# SCH8_BBB.net
KiCad netlist of a schematic drawn in Altium Designer
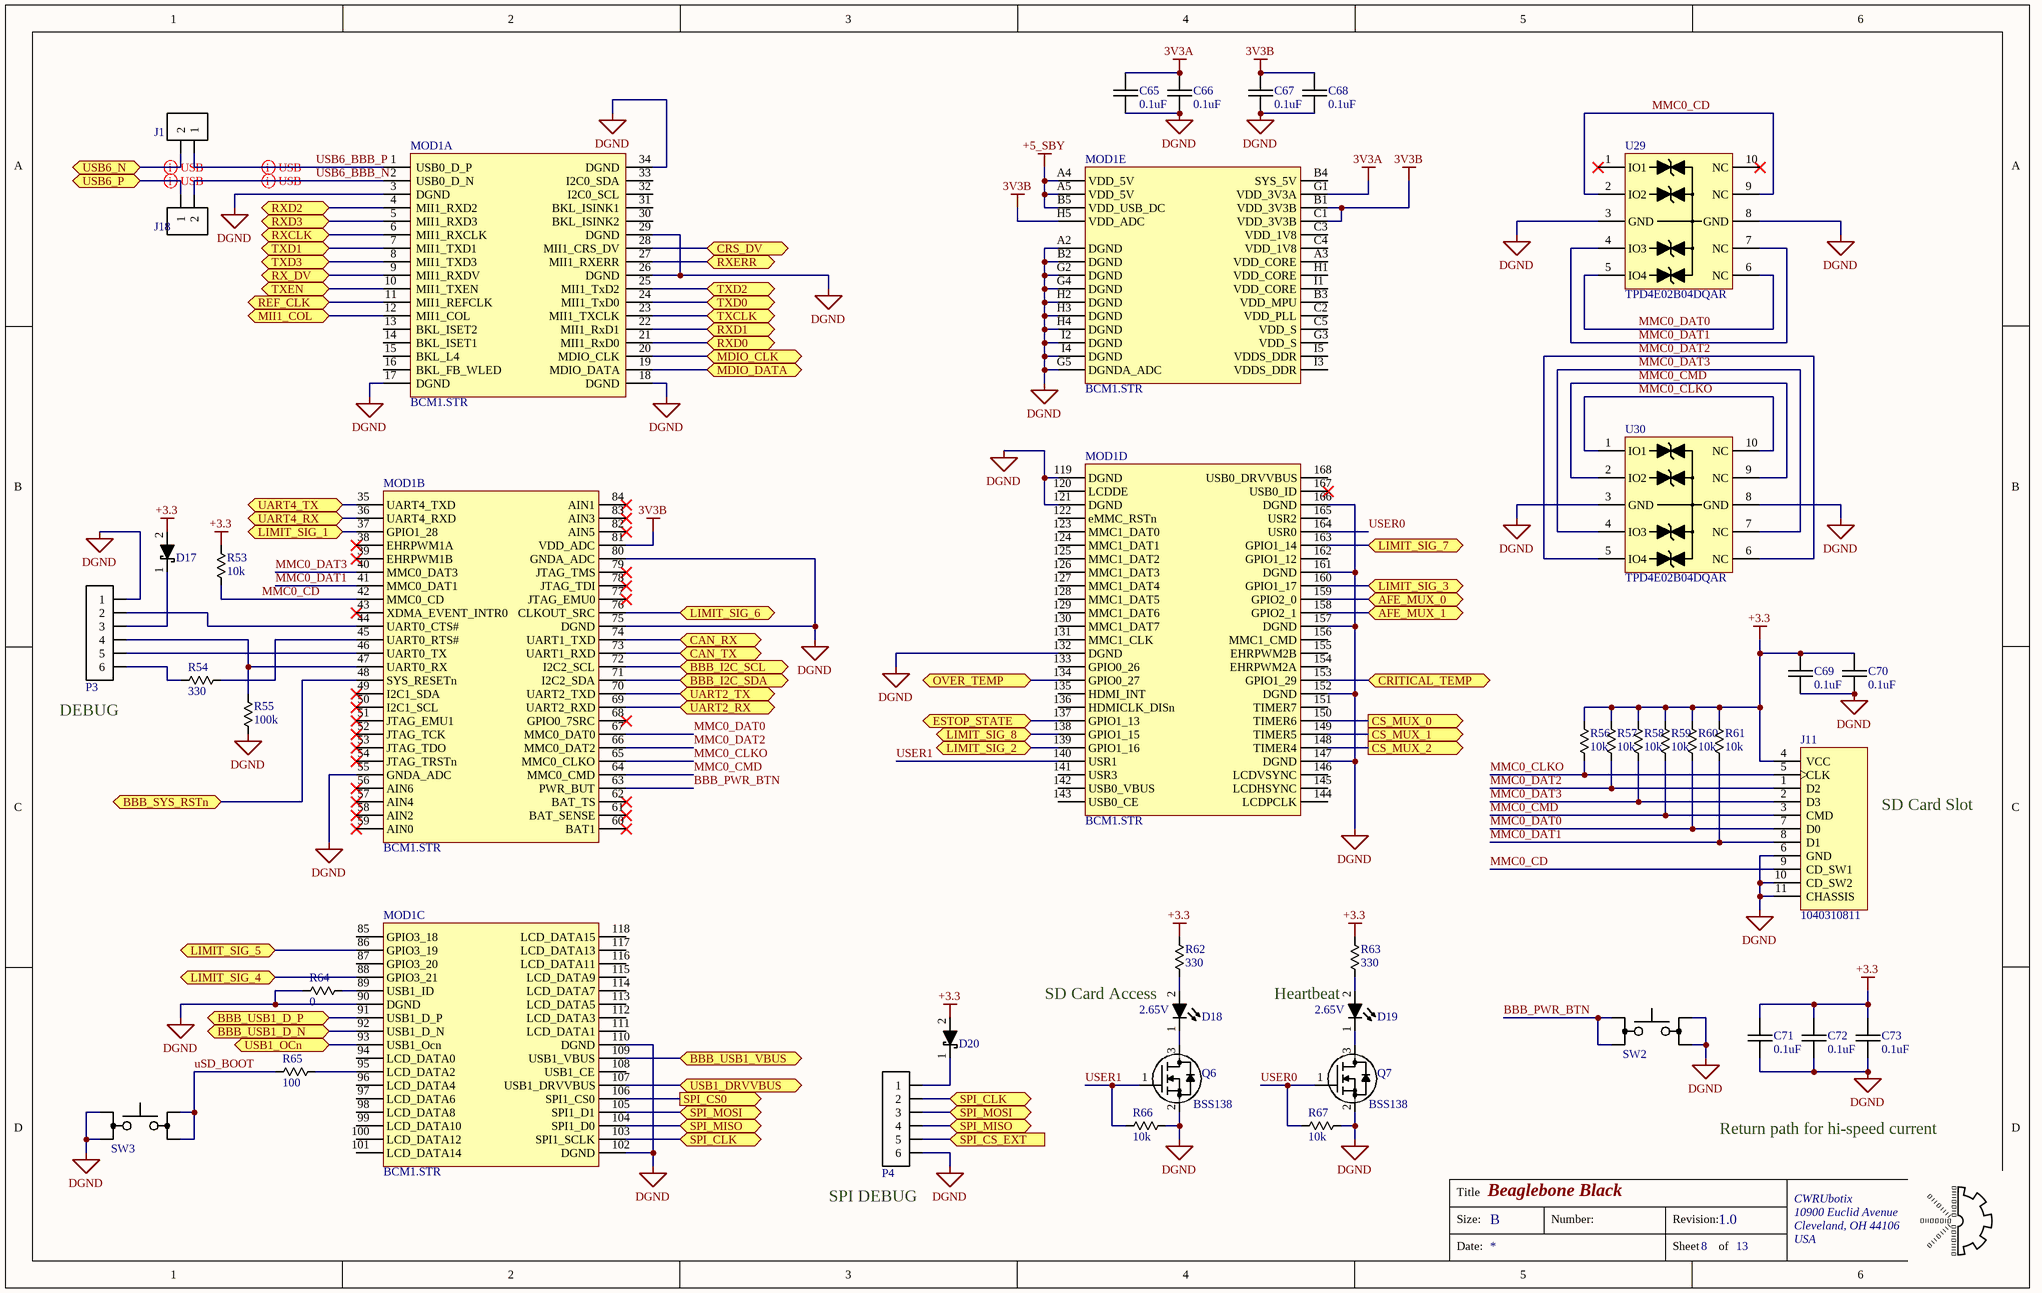
[diagram p0: SCH8_BBB.SchDoc]

(export (version "E")
  (design (tool "Eeschema 10.0.6"))
  (components
    (comp (ref "C65")
      (value "0.1uF")
      (footprint "chip_0603")
      (description "CAP, 0.1uF, ±10%, 16V, X7R, 0603")
      (fields (field (name "PART NUMBER") "CAP-00542") (field (name "TOLERANCE") "±10%"))
      (libsource (lib "Capacitors$") (part "CAP-00542"))
    )
    (comp (ref "C66")
      (value "0.1uF")
      (footprint "chip_0603")
      (description "CAP, 0.1uF, ±10%, 16V, X7R, 0603")
      (fields (field (name "PART NUMBER") "CAP-00542") (field (name "TOLERANCE") "±10%"))
      (libsource (lib "Capacitors$") (part "CAP-00542"))
    )
    (comp (ref "C67")
      (value "0.1uF")
      (footprint "chip_0603")
      (description "CAP, 0.1uF, ±10%, 16V, X7R, 0603")
      (fields (field (name "PART NUMBER") "CAP-00542") (field (name "TOLERANCE") "±10%"))
      (libsource (lib "Capacitors$") (part "CAP-00542"))
    )
    (comp (ref "C68")
      (value "0.1uF")
      (footprint "chip_0603")
      (description "CAP, 0.1uF, ±10%, 16V, X7R, 0603")
      (fields (field (name "PART NUMBER") "CAP-00542") (field (name "TOLERANCE") "±10%"))
      (libsource (lib "Capacitors$") (part "CAP-00542"))
    )
    (comp (ref "C69")
      (value "0.1uF")
      (footprint "chip_0603")
      (description "CAP, 0.1uF, ±10%, 16V, X7R, 0603")
      (fields (field (name "PART NUMBER") "CAP-00542") (field (name "TOLERANCE") "±10%"))
      (libsource (lib "Capacitors$") (part "CAP-00542"))
    )
    (comp (ref "C70")
      (value "0.1uF")
      (footprint "chip_0603")
      (description "CAP, 0.1uF, ±10%, 16V, X7R, 0603")
      (fields (field (name "PART NUMBER") "CAP-00542") (field (name "TOLERANCE") "±10%"))
      (libsource (lib "Capacitors$") (part "CAP-00542"))
    )
    (comp (ref "C71")
      (value "0.1uF")
      (footprint "chip_0603")
      (description "CAP, 0.1uF, ±10%, 16V, X7R, 0603")
      (fields (field (name "PART NUMBER") "CAP-00542") (field (name "TOLERANCE") "±10%"))
      (libsource (lib "Capacitors$") (part "CAP-00542"))
    )
    (comp (ref "C72")
      (value "0.1uF")
      (footprint "chip_0603")
      (description "CAP, 0.1uF, ±10%, 16V, X7R, 0603")
      (fields (field (name "PART NUMBER") "CAP-00542") (field (name "TOLERANCE") "±10%"))
      (libsource (lib "Capacitors$") (part "CAP-00542"))
    )
    (comp (ref "C73")
      (value "0.1uF")
      (footprint "chip_0603")
      (description "CAP, 0.1uF, ±10%, 16V, X7R, 0603")
      (fields (field (name "PART NUMBER") "CAP-00542") (field (name "TOLERANCE") "±10%"))
      (libsource (lib "Capacitors$") (part "CAP-00542"))
    )
    (comp (ref "D17")
      (value "diode_2")
      (footprint "sod123_0")
      (description "Dio Shtky, 1A, 0.55V, 40V, SOD-123")
      (fields (field (name "PART NUMBER") "DIO-00001") (field (name "MANUFACTURER") "ON Semi"))
      (libsource (lib "Diodes$") (part "DIO-00001"))
    )
    (comp (ref "D18")
      (value "diode_4")
      (footprint "chip_0603_LED")
      (description "LED, Blue, 0603, Low current, HELI2 Series")
      (fields
        (field (name "PART NUMBER") "DIO-00049")
        (field (name "FORWARD VOLTAGE") "2.65V")
        (field (name "MANUFACTURER") "Kingbright")
      )
      (libsource (lib "Diodes$") (part "DIO-00049"))
    )
    (comp (ref "D19")
      (value "diode_4")
      (footprint "chip_0603_LED")
      (description "LED, Blue, 0603, Low current, HELI2 Series")
      (fields
        (field (name "PART NUMBER") "DIO-00049")
        (field (name "FORWARD VOLTAGE") "2.65V")
        (field (name "MANUFACTURER") "Kingbright")
      )
      (libsource (lib "Diodes$") (part "DIO-00049"))
    )
    (comp (ref "D20")
      (value "diode_2")
      (footprint "sod123_0")
      (description "Dio Shtky, 1A, 0.55V, 40V, SOD-123")
      (fields (field (name "PART NUMBER") "DIO-00001") (field (name "MANUFACTURER") "ON Semi"))
      (libsource (lib "Diodes$") (part "DIO-00001"))
    )
    (comp (ref "J1")
      (value "conn-2x1_0")
      (footprint "HDDR_2x1_0")
      (description "Header, 2x1, 0.1\"")
      (fields (field (name "PART NUMBER") "CONN-00055") (field (name "MANUFACTURER") "Samtec"))
      (libsource (lib "Connectors$") (part "CONN-00055"))
    )
    (comp (ref "J11")
      (value "1040310811")
      (footprint "MOLEX_1040310811")
      (description "Micro SD Card Slot, Push-Pull w/ Card-Detect Switch, SMD, Molex")
      (fields (field (name "PART NUMBER") "CONN-00091") (field (name "MANUFACTURER") "Molex"))
      (libsource (lib "Connectors$") (part "CONN-00091"))
    )
    (comp (ref "J18")
      (value "conn-2x1_0")
      (footprint "HDDR_2x1_0")
      (description "Header, 2x1, 0.1\"")
      (fields (field (name "PART NUMBER") "CONN-00055") (field (name "MANUFACTURER") "Samtec"))
      (libsource (lib "Connectors$") (part "CONN-00055"))
    )
    (comp (ref "MOD1")
      (value "BCM1.STR")
      (footprint "BEAGLECORE_BCM1")
      (description "BeagleCore BCM1, System-On-Module (SOM)")
      (fields (field (name "PART NUMBER") "UCTRL-00011") (field (name "MANUFACTURER") "BeagleCore"))
      (libsource (lib "Microcontrollers$") (part "UCTRL-00011"))
    )
    (comp (ref "P3")
      (value "conn-6x1_0")
      (footprint "HDDR_6X1_0")
      (description "Header 6x1, 0.1\"")
      (fields (field (name "PART NUMBER") "CONN-00008"))
      (libsource (lib "Connectors$") (part "CONN-00008"))
    )
    (comp (ref "P4")
      (value "conn-6x1_0")
      (footprint "HDDR_6X1_0")
      (description "Header 6x1, 0.1\"")
      (fields (field (name "PART NUMBER") "CONN-00008"))
      (libsource (lib "Connectors$") (part "CONN-00008"))
    )
    (comp (ref "Q6")
      (value "n-mosfet_1")
      (footprint "sot-23-3")
      (description "XSTR NMOS, 220mA, 50V, Vgs 1.3V, SOT-23-3")
      (fields
        (field (name "PART NUMBER") "XSTR-00017")
        (field (name "MANUFACTURER") "ON Semi")
        (field (name "MANUFACTURER PN") "BSS138")
      )
      (libsource (lib "Transistors$") (part "XSTR-00017"))
    )
    (comp (ref "Q7")
      (value "n-mosfet_1")
      (footprint "sot-23-3")
      (description "XSTR NMOS, 220mA, 50V, Vgs 1.3V, SOT-23-3")
      (fields
        (field (name "PART NUMBER") "XSTR-00017")
        (field (name "MANUFACTURER") "ON Semi")
        (field (name "MANUFACTURER PN") "BSS138")
      )
      (libsource (lib "Transistors$") (part "XSTR-00017"))
    )
    (comp (ref "R53")
      (value "10k")
      (footprint "chip_0603")
      (description "RES SMD 10K OHM 1% 1/4W 0603")
      (fields (field (name "PART NUMBER") "RES-00306") (field (name "TOLERANCE") "1%"))
      (libsource (lib "Resistors$") (part "RES-00306"))
    )
    (comp (ref "R54")
      (value "330")
      (footprint "chip_0603")
      (description "RES SMD 330 OHM 1% 1/4W 0603")
      (fields (field (name "PART NUMBER") "RES-00221") (field (name "TOLERANCE") "1%"))
      (libsource (lib "Resistors$") (part "RES-00221"))
    )
    (comp (ref "R55")
      (value "100k")
      (footprint "chip_0603")
      (description "RES SMD 100K OHM 1% 1/4W 0603")
      (fields (field (name "PART NUMBER") "RES-00301") (field (name "TOLERANCE") "1%"))
      (libsource (lib "Resistors$") (part "RES-00301"))
    )
    (comp (ref "R56")
      (value "10k")
      (footprint "chip_0603")
      (description "RES SMD 10K OHM 1% 1/4W 0603")
      (fields (field (name "PART NUMBER") "RES-00306") (field (name "TOLERANCE") "1%"))
      (libsource (lib "Resistors$") (part "RES-00306"))
    )
    (comp (ref "R57")
      (value "10k")
      (footprint "chip_0603")
      (description "RES SMD 10K OHM 1% 1/4W 0603")
      (fields (field (name "PART NUMBER") "RES-00306") (field (name "TOLERANCE") "1%"))
      (libsource (lib "Resistors$") (part "RES-00306"))
    )
    (comp (ref "R58")
      (value "10k")
      (footprint "chip_0603")
      (description "RES SMD 10K OHM 1% 1/4W 0603")
      (fields (field (name "PART NUMBER") "RES-00306") (field (name "TOLERANCE") "1%"))
      (libsource (lib "Resistors$") (part "RES-00306"))
    )
    (comp (ref "R59")
      (value "10k")
      (footprint "chip_0603")
      (description "RES SMD 10K OHM 1% 1/4W 0603")
      (fields (field (name "PART NUMBER") "RES-00306") (field (name "TOLERANCE") "1%"))
      (libsource (lib "Resistors$") (part "RES-00306"))
    )
    (comp (ref "R60")
      (value "10k")
      (footprint "chip_0603")
      (description "RES SMD 10K OHM 1% 1/4W 0603")
      (fields (field (name "PART NUMBER") "RES-00306") (field (name "TOLERANCE") "1%"))
      (libsource (lib "Resistors$") (part "RES-00306"))
    )
    (comp (ref "R61")
      (value "10k")
      (footprint "chip_0603")
      (description "RES SMD 10K OHM 1% 1/4W 0603")
      (fields (field (name "PART NUMBER") "RES-00306") (field (name "TOLERANCE") "1%"))
      (libsource (lib "Resistors$") (part "RES-00306"))
    )
    (comp (ref "R62")
      (value "330")
      (footprint "chip_0603")
      (description "RES SMD 330 OHM 1% 1/4W 0603")
      (fields (field (name "PART NUMBER") "RES-00221") (field (name "TOLERANCE") "1%"))
      (libsource (lib "Resistors$") (part "RES-00221"))
    )
    (comp (ref "R63")
      (value "330")
      (footprint "chip_0603")
      (description "RES SMD 330 OHM 1% 1/4W 0603")
      (fields (field (name "PART NUMBER") "RES-00221") (field (name "TOLERANCE") "1%"))
      (libsource (lib "Resistors$") (part "RES-00221"))
    )
    (comp (ref "R64")
      (value "0")
      (footprint "chip_0805")
      (description "RES SMD 0 OHM 1/8W 0805 Thick Film")
      (fields (field (name "PART NUMBER") "RES-00720") (field (name "TOLERANCE") "Jumper"))
      (libsource (lib "Resistors$") (part "RES-00720"))
    )
    (comp (ref "R65")
      (value "100")
      (footprint "chip_0603")
      (description "RES SMD 100 OHM 1% 1/4W 0603")
      (fields (field (name "PART NUMBER") "RES-00178") (field (name "TOLERANCE") "1%"))
      (libsource (lib "Resistors$") (part "RES-00178"))
    )
    (comp (ref "R66")
      (value "10k")
      (footprint "chip_0603")
      (description "RES SMD 10K OHM 1% 1/4W 0603")
      (fields (field (name "PART NUMBER") "RES-00306") (field (name "TOLERANCE") "1%"))
      (libsource (lib "Resistors$") (part "RES-00306"))
    )
    (comp (ref "R67")
      (value "10k")
      (footprint "chip_0603")
      (description "RES SMD 10K OHM 1% 1/4W 0603")
      (fields (field (name "PART NUMBER") "RES-00306") (field (name "TOLERANCE") "1%"))
      (libsource (lib "Resistors$") (part "RES-00306"))
    )
    (comp (ref "SW2")
      (value "SW_1P1T_2")
      (footprint "B3FS-1000")
      (description "Switch, SPST-NO, Tactile, 6.3x6.0mm, SMD, 50mA 24VDC")
      (fields (field (name "PART NUMBER") "MISC-00042") (field (name "MANUFACTURER") "Omron"))
      (libsource (lib "Misc$") (part "MISC-00042"))
    )
    (comp (ref "SW3")
      (value "SW_1P1T_2")
      (footprint "B3FS-1000")
      (description "Switch, SPST-NO, Tactile, 6.3x6.0mm, SMD, 50mA 24VDC")
      (fields (field (name "PART NUMBER") "MISC-00042") (field (name "MANUFACTURER") "Omron"))
      (libsource (lib "Misc$") (part "MISC-00042"))
    )
    (comp (ref "U29")
      (value "TPD4E02B04DQAR")
      (footprint "USON-10")
      (description "TVS, 4-Ch, ESD Protec, 3.6V 8.8V 10-USON")
      (fields (field (name "PART NUMBER") "DIO-00068") (field (name "MANUFACTURER") "TI"))
      (libsource (lib "Diodes$") (part "DIO-00068"))
    )
    (comp (ref "U30")
      (value "TPD4E02B04DQAR")
      (footprint "USON-10")
      (description "TVS, 4-Ch, ESD Protec, 3.6V 8.8V 10-USON")
      (fields (field (name "PART NUMBER") "DIO-00068") (field (name "MANUFACTURER") "TI"))
      (libsource (lib "Diodes$") (part "DIO-00068"))
    )
  )
  (nets
    (net (code "1") (name "+3.3") (class "Default")
      (node (ref "C69") (pin "2") (pinfunction "2_2") (pintype "passive"))
      (node (ref "C70") (pin "2") (pinfunction "2_2") (pintype "passive"))
      (node (ref "C71") (pin "2") (pinfunction "2_2") (pintype "passive"))
      (node (ref "C72") (pin "2") (pinfunction "2_2") (pintype "passive"))
      (node (ref "C73") (pin "2") (pinfunction "2_2") (pintype "passive"))
      (node (ref "D17") (pin "2") (pinfunction "2_2") (pintype "passive"))
      (node (ref "D20") (pin "2") (pinfunction "2_2") (pintype "passive"))
      (node (ref "J11") (pin "4") (pinfunction "VCC_4") (pintype "passive"))
      (node (ref "R53") (pin "1") (pinfunction "1_1") (pintype "passive"))
      (node (ref "R56") (pin "1") (pinfunction "1_1") (pintype "passive"))
      (node (ref "R57") (pin "1") (pinfunction "1_1") (pintype "passive"))
      (node (ref "R58") (pin "1") (pinfunction "1_1") (pintype "passive"))
      (node (ref "R59") (pin "1") (pinfunction "1_1") (pintype "passive"))
      (node (ref "R60") (pin "1") (pinfunction "1_1") (pintype "passive"))
      (node (ref "R61") (pin "1") (pinfunction "1_1") (pintype "passive"))
      (node (ref "R62") (pin "2") (pinfunction "2_2") (pintype "passive"))
      (node (ref "R63") (pin "2") (pinfunction "2_2") (pintype "passive"))
    )
    (net (code "2") (name "+5_SBY") (class "Default")
      (node (ref "MOD1") (pin "A4") (pinfunction "VDD_5V_A4") (pintype "passive"))
      (node (ref "MOD1") (pin "A5") (pinfunction "VDD_5V_A5") (pintype "passive"))
      (node (ref "MOD1") (pin "B5") (pinfunction "VDD_USB_DC_B5") (pintype "passive"))
    )
    (net (code "3") (name "/AFE_MUX_0") (class "Default")
      (node (ref "MOD1") (pin "159") (pinfunction "GPIO2_0_159") (pintype "passive"))
    )
    (net (code "4") (name "/AFE_MUX_1") (class "Default")
      (node (ref "MOD1") (pin "158") (pinfunction "GPIO2_1_158") (pintype "passive"))
    )
    (net (code "5") (name "/BBB_I2C_SCL") (class "Default")
      (node (ref "MOD1") (pin "72") (pinfunction "I2C2_SCL_72") (pintype "passive"))
    )
    (net (code "6") (name "/BBB_I2C_SDA") (class "Default")
      (node (ref "MOD1") (pin "71") (pinfunction "I2C2_SDA_71") (pintype "passive"))
    )
    (net (code "7") (name "/BBB_PWR_BTN") (class "Default")
      (node (ref "MOD1") (pin "63") (pinfunction "PWR_BUT_63") (pintype "passive"))
      (node (ref "SW2") (pin "1") (pinfunction "1_1") (pintype "passive"))
      (node (ref "SW2") (pin "2") (pinfunction "2_2") (pintype "passive"))
    )
    (net (code "8") (name "/BBB_SYS_RSTn") (class "Default")
      (node (ref "MOD1") (pin "48") (pinfunction "SYS_RESETn_48") (pintype "passive"))
    )
    (net (code "9") (name "/BBB_USB1_D_N") (class "Default")
      (node (ref "MOD1") (pin "92") (pinfunction "USB1_D_N_92") (pintype "passive"))
    )
    (net (code "10") (name "/BBB_USB1_D_P") (class "Default")
      (node (ref "MOD1") (pin "91") (pinfunction "USB1_D_P_91") (pintype "passive"))
    )
    (net (code "11") (name "/BBB_USB1_VBUS") (class "Default")
      (node (ref "MOD1") (pin "109") (pinfunction "USB1_VBUS_109") (pintype "passive"))
    )
    (net (code "12") (name "/CAN_RX") (class "Default")
      (node (ref "MOD1") (pin "74") (pinfunction "UART1_TXD_74") (pintype "passive"))
    )
    (net (code "13") (name "/CAN_TX") (class "Default")
      (node (ref "MOD1") (pin "73") (pinfunction "UART1_RXD_73") (pintype "passive"))
    )
    (net (code "14") (name "/CRITICAL_TEMP") (class "Default")
      (node (ref "MOD1") (pin "153") (pinfunction "GPIO1_29_153") (pintype "passive"))
    )
    (net (code "15") (name "/CRS_DV") (class "Default")
      (node (ref "MOD1") (pin "28") (pinfunction "MII1_CRS_DV_28") (pintype "passive"))
    )
    (net (code "16") (name "/CS_MUX_0") (class "Default")
      (node (ref "MOD1") (pin "150") (pinfunction "TIMER6_150") (pintype "passive"))
    )
    (net (code "17") (name "/CS_MUX_1") (class "Default")
      (node (ref "MOD1") (pin "149") (pinfunction "TIMER5_149") (pintype "passive"))
    )
    (net (code "18") (name "/CS_MUX_2") (class "Default")
      (node (ref "MOD1") (pin "148") (pinfunction "TIMER4_148") (pintype "passive"))
    )
    (net (code "19") (name "/ESTOP_STATE") (class "Default")
      (node (ref "MOD1") (pin "137") (pinfunction "GPIO1_13_137") (pintype "passive"))
    )
    (net (code "20") (name "/LIMIT_SIG_1") (class "Default")
      (node (ref "MOD1") (pin "37") (pinfunction "GPIO1_28_37") (pintype "passive"))
    )
    (net (code "21") (name "/LIMIT_SIG_2") (class "Default")
      (node (ref "MOD1") (pin "139") (pinfunction "GPIO1_16_139") (pintype "passive"))
    )
    (net (code "22") (name "/LIMIT_SIG_3") (class "Default")
      (node (ref "MOD1") (pin "160") (pinfunction "GPIO1_17_160") (pintype "passive"))
    )
    (net (code "23") (name "/LIMIT_SIG_4") (class "Default")
      (node (ref "MOD1") (pin "88") (pinfunction "GPIO3_21_88") (pintype "passive"))
    )
    (net (code "24") (name "/LIMIT_SIG_5") (class "Default")
      (node (ref "MOD1") (pin "86") (pinfunction "GPIO3_19_86") (pintype "passive"))
    )
    (net (code "25") (name "/LIMIT_SIG_6") (class "Default")
      (node (ref "MOD1") (pin "76") (pinfunction "CLKOUT_SRC_76") (pintype "passive"))
    )
    (net (code "26") (name "/LIMIT_SIG_7") (class "Default")
      (node (ref "MOD1") (pin "163") (pinfunction "GPIO1_14_163") (pintype "passive"))
    )
    (net (code "27") (name "/LIMIT_SIG_8") (class "Default")
      (node (ref "MOD1") (pin "138") (pinfunction "GPIO1_15_138") (pintype "passive"))
    )
    (net (code "28") (name "/MDIO_CLK") (class "Default")
      (node (ref "MOD1") (pin "20") (pinfunction "MDIO_CLK_20") (pintype "passive"))
    )
    (net (code "29") (name "/MDIO_DATA") (class "Default")
      (node (ref "MOD1") (pin "19") (pinfunction "MDIO_DATA_19") (pintype "passive"))
    )
    (net (code "30") (name "/MII1_COL") (class "Default")
      (node (ref "MOD1") (pin "12") (pinfunction "MII1_COL_12") (pintype "passive"))
    )
    (net (code "31") (name "/MMC0_CD") (class "Default")
      (node (ref "J11") (pin "9") (pinfunction "CD_SW1_9") (pintype "passive"))
      (node (ref "MOD1") (pin "42") (pinfunction "MMC0_CD_42") (pintype "passive"))
      (node (ref "R53") (pin "2") (pinfunction "2_2") (pintype "passive"))
      (node (ref "U29") (pin "2") (pinfunction "IO2_2") (pintype "passive"))
      (node (ref "U29") (pin "9") (pinfunction "NC_9") (pintype "passive"))
    )
    (net (code "32") (name "/MMC0_CLKO") (class "Default")
      (node (ref "J11") (pin "5") (pinfunction "CLK_5") (pintype "passive"))
      (node (ref "MOD1") (pin "65") (pinfunction "MMC0_CLKO_65") (pintype "passive"))
      (node (ref "R56") (pin "2") (pinfunction "2_2") (pintype "passive"))
      (node (ref "U30") (pin "1") (pinfunction "IO1_1") (pintype "passive"))
      (node (ref "U30") (pin "10") (pinfunction "NC_10") (pintype "passive"))
    )
    (net (code "33") (name "/MMC0_CMD") (class "Default")
      (node (ref "J11") (pin "3") (pinfunction "CMD_3") (pintype "passive"))
      (node (ref "MOD1") (pin "64") (pinfunction "MMC0_CMD_64") (pintype "passive"))
      (node (ref "R59") (pin "2") (pinfunction "2_2") (pintype "passive"))
      (node (ref "U30") (pin "2") (pinfunction "IO2_2") (pintype "passive"))
      (node (ref "U30") (pin "9") (pinfunction "NC_9") (pintype "passive"))
    )
    (net (code "34") (name "/MMC0_DAT0") (class "Default")
      (node (ref "J11") (pin "7") (pinfunction "D0_7") (pintype "passive"))
      (node (ref "MOD1") (pin "67") (pinfunction "MMC0_DAT0_67") (pintype "passive"))
      (node (ref "R60") (pin "2") (pinfunction "2_2") (pintype "passive"))
      (node (ref "U29") (pin "5") (pinfunction "IO4_5") (pintype "passive"))
      (node (ref "U29") (pin "6") (pinfunction "NC_6") (pintype "passive"))
    )
    (net (code "35") (name "/MMC0_DAT1") (class "Default")
      (node (ref "J11") (pin "8") (pinfunction "D1_8") (pintype "passive"))
      (node (ref "MOD1") (pin "41") (pinfunction "MMC0_DAT1_41") (pintype "passive"))
      (node (ref "R61") (pin "2") (pinfunction "2_2") (pintype "passive"))
      (node (ref "U29") (pin "4") (pinfunction "IO3_4") (pintype "passive"))
      (node (ref "U29") (pin "7") (pinfunction "NC_7") (pintype "passive"))
    )
    (net (code "36") (name "/MMC0_DAT2") (class "Default")
      (node (ref "J11") (pin "1") (pinfunction "D2_1") (pintype "passive"))
      (node (ref "MOD1") (pin "66") (pinfunction "MMC0_DAT2_66") (pintype "passive"))
      (node (ref "R57") (pin "2") (pinfunction "2_2") (pintype "passive"))
      (node (ref "U30") (pin "5") (pinfunction "IO4_5") (pintype "passive"))
      (node (ref "U30") (pin "6") (pinfunction "NC_6") (pintype "passive"))
    )
    (net (code "37") (name "/MMC0_DAT3") (class "Default")
      (node (ref "J11") (pin "2") (pinfunction "D3_2") (pintype "passive"))
      (node (ref "MOD1") (pin "40") (pinfunction "MMC0_DAT3_40") (pintype "passive"))
      (node (ref "R58") (pin "2") (pinfunction "2_2") (pintype "passive"))
      (node (ref "U30") (pin "4") (pinfunction "IO3_4") (pintype "passive"))
      (node (ref "U30") (pin "7") (pinfunction "NC_7") (pintype "passive"))
    )
    (net (code "38") (name "/OVER_TEMP") (class "Default")
      (node (ref "MOD1") (pin "134") (pinfunction "GPIO0_27_134") (pintype "passive"))
    )
    (net (code "39") (name "/REF_CLK") (class "Default")
      (node (ref "MOD1") (pin "11") (pinfunction "MII1_REFCLK_11") (pintype "passive"))
    )
    (net (code "40") (name "/RXCLK") (class "Default")
      (node (ref "MOD1") (pin "6") (pinfunction "MII1_RXCLK_6") (pintype "passive"))
    )
    (net (code "41") (name "/RXD0") (class "Default")
      (node (ref "MOD1") (pin "21") (pinfunction "MII1_RxD0_21") (pintype "passive"))
    )
    (net (code "42") (name "/RXD1") (class "Default")
      (node (ref "MOD1") (pin "22") (pinfunction "MII1_RxD1_22") (pintype "passive"))
    )
    (net (code "43") (name "/RXD2") (class "Default")
      (node (ref "MOD1") (pin "4") (pinfunction "MII1_RXD2_4") (pintype "passive"))
    )
    (net (code "44") (name "/RXD3") (class "Default")
      (node (ref "MOD1") (pin "5") (pinfunction "MII1_RXD3_5") (pintype "passive"))
    )
    (net (code "45") (name "/RXERR") (class "Default")
      (node (ref "MOD1") (pin "27") (pinfunction "MII1_RXERR_27") (pintype "passive"))
    )
    (net (code "46") (name "/RX_DV") (class "Default")
      (node (ref "MOD1") (pin "9") (pinfunction "MII1_RXDV_9") (pintype "passive"))
    )
    (net (code "47") (name "/SPI_CLK") (class "Default")
      (node (ref "MOD1") (pin "103") (pinfunction "SPI1_SCLK_103") (pintype "passive"))
      (node (ref "P4") (pin "2") (pinfunction "2_2") (pintype "passive"))
    )
    (net (code "48") (name "/SPI_CS0") (class "Default")
      (node (ref "MOD1") (pin "106") (pinfunction "SPI1_CS0_106") (pintype "passive"))
    )
    (net (code "49") (name "/SPI_CS_EXT") (class "Default")
      (node (ref "P4") (pin "5") (pinfunction "5_5") (pintype "passive"))
    )
    (net (code "50") (name "/SPI_MISO") (class "Default")
      (node (ref "MOD1") (pin "104") (pinfunction "SPI1_D0_104") (pintype "passive"))
      (node (ref "P4") (pin "4") (pinfunction "4_4") (pintype "passive"))
    )
    (net (code "51") (name "/SPI_MOSI") (class "Default")
      (node (ref "MOD1") (pin "105") (pinfunction "SPI1_D1_105") (pintype "passive"))
      (node (ref "P4") (pin "3") (pinfunction "3_3") (pintype "passive"))
    )
    (net (code "52") (name "/TXCLK") (class "Default")
      (node (ref "MOD1") (pin "23") (pinfunction "MII1_TXCLK_23") (pintype "passive"))
    )
    (net (code "53") (name "/TXD0") (class "Default")
      (node (ref "MOD1") (pin "24") (pinfunction "MII1_TxD0_24") (pintype "passive"))
    )
    (net (code "54") (name "/TXD1") (class "Default")
      (node (ref "MOD1") (pin "7") (pinfunction "MII1_TXD1_7") (pintype "passive"))
    )
    (net (code "55") (name "/TXD2") (class "Default")
      (node (ref "MOD1") (pin "25") (pinfunction "MII1_TxD2_25") (pintype "passive"))
    )
    (net (code "56") (name "/TXD3") (class "Default")
      (node (ref "MOD1") (pin "8") (pinfunction "MII1_TXD3_8") (pintype "passive"))
    )
    (net (code "57") (name "/TXEN") (class "Default")
      (node (ref "MOD1") (pin "10") (pinfunction "MII1_TXEN_10") (pintype "passive"))
    )
    (net (code "58") (name "/UART2_RX") (class "Default")
      (node (ref "MOD1") (pin "69") (pinfunction "UART2_RXD_69") (pintype "passive"))
    )
    (net (code "59") (name "/UART2_TX") (class "Default")
      (node (ref "MOD1") (pin "70") (pinfunction "UART2_TXD_70") (pintype "passive"))
    )
    (net (code "60") (name "/UART4_RX") (class "Default")
      (node (ref "MOD1") (pin "36") (pinfunction "UART4_RXD_36") (pintype "passive"))
    )
    (net (code "61") (name "/UART4_TX") (class "Default")
      (node (ref "MOD1") (pin "35") (pinfunction "UART4_TXD_35") (pintype "passive"))
    )
    (net (code "62") (name "/USB1_DRVVBUS") (class "Default")
      (node (ref "MOD1") (pin "107") (pinfunction "USB1_DRVVBUS_107") (pintype "passive"))
    )
    (net (code "63") (name "/USB1_OCn") (class "Default")
      (node (ref "MOD1") (pin "93") (pinfunction "USB1_Ocn_93") (pintype "passive"))
    )
    (net (code "64") (name "/USB6_BBB_N") (class "Default")
      (node (ref "J18") (pin "2") (pinfunction "2_2") (pintype "passive"))
      (node (ref "MOD1") (pin "2") (pinfunction "USB0_D_N_2") (pintype "passive"))
    )
    (net (code "65") (name "/USB6_BBB_P") (class "Default")
      (node (ref "J1") (pin "1") (pinfunction "1_1") (pintype "passive"))
      (node (ref "MOD1") (pin "1") (pinfunction "USB0_D_P_1") (pintype "passive"))
    )
    (net (code "66") (name "/USB6_N") (class "Default")
      (node (ref "J1") (pin "2") (pinfunction "2_2") (pintype "passive"))
    )
    (net (code "67") (name "/USB6_P") (class "Default")
      (node (ref "J18") (pin "1") (pinfunction "1_1") (pintype "passive"))
    )
    (net (code "68") (name "/USER0") (class "Default")
      (node (ref "MOD1") (pin "164") (pinfunction "USR0_164") (pintype "passive"))
      (node (ref "Q7") (pin "1") (pinfunction "G_1") (pintype "passive"))
      (node (ref "R67") (pin "1") (pinfunction "1_1") (pintype "passive"))
    )
    (net (code "69") (name "/USER1") (class "Default")
      (node (ref "MOD1") (pin "140") (pinfunction "USR1_140") (pintype "passive"))
      (node (ref "Q6") (pin "1") (pinfunction "G_1") (pintype "passive"))
      (node (ref "R66") (pin "1") (pinfunction "1_1") (pintype "passive"))
    )
    (net (code "70") (name "/uSD_BOOT") (class "Default")
      (node (ref "R65") (pin "1") (pinfunction "1_1") (pintype "passive"))
      (node (ref "SW3") (pin "3") (pinfunction "3_3") (pintype "passive"))
      (node (ref "SW3") (pin "4") (pinfunction "4_4") (pintype "passive"))
    )
    (net (code "71") (name "3V3A") (class "Default")
      (node (ref "C65") (pin "2") (pinfunction "2_2") (pintype "passive"))
      (node (ref "C66") (pin "2") (pinfunction "2_2") (pintype "passive"))
      (node (ref "MOD1") (pin "G1") (pinfunction "VDD_3V3A_G1") (pintype "passive"))
    )
    (net (code "72") (name "3V3B") (class "Default")
      (node (ref "C67") (pin "2") (pinfunction "2_2") (pintype "passive"))
      (node (ref "C68") (pin "2") (pinfunction "2_2") (pintype "passive"))
      (node (ref "MOD1") (pin "81") (pinfunction "VDD_ADC_81") (pintype "passive"))
      (node (ref "MOD1") (pin "B1") (pinfunction "VDD_3V3B_B1") (pintype "passive"))
      (node (ref "MOD1") (pin "C1") (pinfunction "VDD_3V3B_C1") (pintype "passive"))
      (node (ref "MOD1") (pin "H5") (pinfunction "VDD_ADC_H5") (pintype "passive"))
    )
    (net (code "73") (name "DGND") (class "Default")
      (node (ref "C65") (pin "1") (pinfunction "1_1") (pintype "passive"))
      (node (ref "C66") (pin "1") (pinfunction "1_1") (pintype "passive"))
      (node (ref "C67") (pin "1") (pinfunction "1_1") (pintype "passive"))
      (node (ref "C68") (pin "1") (pinfunction "1_1") (pintype "passive"))
      (node (ref "C69") (pin "1") (pinfunction "1_1") (pintype "passive"))
      (node (ref "C70") (pin "1") (pinfunction "1_1") (pintype "passive"))
      (node (ref "C71") (pin "1") (pinfunction "1_1") (pintype "passive"))
      (node (ref "C72") (pin "1") (pinfunction "1_1") (pintype "passive"))
      (node (ref "C73") (pin "1") (pinfunction "1_1") (pintype "passive"))
      (node (ref "J11") (pin "10") (pinfunction "CD_SW2_10") (pintype "passive"))
      (node (ref "J11") (pin "11") (pinfunction "CHASSIS_11") (pintype "passive"))
      (node (ref "J11") (pin "6") (pinfunction "GND_6") (pintype "passive"))
      (node (ref "MOD1") (pin "102") (pinfunction "DGND_102") (pintype "passive"))
      (node (ref "MOD1") (pin "110") (pinfunction "DGND_110") (pintype "passive"))
      (node (ref "MOD1") (pin "119") (pinfunction "DGND_119") (pintype "passive"))
      (node (ref "MOD1") (pin "121") (pinfunction "DGND_121") (pintype "passive"))
      (node (ref "MOD1") (pin "132") (pinfunction "DGND_132") (pintype "passive"))
      (node (ref "MOD1") (pin "147") (pinfunction "DGND_147") (pintype "passive"))
      (node (ref "MOD1") (pin "152") (pinfunction "DGND_152") (pintype "passive"))
      (node (ref "MOD1") (pin "157") (pinfunction "DGND_157") (pintype "passive"))
      (node (ref "MOD1") (pin "161") (pinfunction "DGND_161") (pintype "passive"))
      (node (ref "MOD1") (pin "166") (pinfunction "DGND_166") (pintype "passive"))
      (node (ref "MOD1") (pin "17") (pinfunction "DGND_17") (pintype "passive"))
      (node (ref "MOD1") (pin "18") (pinfunction "DGND_18") (pintype "passive"))
      (node (ref "MOD1") (pin "26") (pinfunction "DGND_26") (pintype "passive"))
      (node (ref "MOD1") (pin "29") (pinfunction "DGND_29") (pintype "passive"))
      (node (ref "MOD1") (pin "3") (pinfunction "DGND_3") (pintype "passive"))
      (node (ref "MOD1") (pin "34") (pinfunction "DGND_34") (pintype "passive"))
      (node (ref "MOD1") (pin "55") (pinfunction "GNDA_ADC_55") (pintype "passive"))
      (node (ref "MOD1") (pin "75") (pinfunction "DGND_75") (pintype "passive"))
      (node (ref "MOD1") (pin "80") (pinfunction "GNDA_ADC_80") (pintype "passive"))
      (node (ref "MOD1") (pin "90") (pinfunction "DGND_90") (pintype "passive"))
      (node (ref "MOD1") (pin "A2") (pinfunction "DGND_A2") (pintype "passive"))
      (node (ref "MOD1") (pin "B2") (pinfunction "DGND_B2") (pintype "passive"))
      (node (ref "MOD1") (pin "G2") (pinfunction "DGND_G2") (pintype "passive"))
      (node (ref "MOD1") (pin "G4") (pinfunction "DGND_G4") (pintype "passive"))
      (node (ref "MOD1") (pin "G5") (pinfunction "DGNDA_ADC_G5") (pintype "passive"))
      (node (ref "MOD1") (pin "H2") (pinfunction "DGND_H2") (pintype "passive"))
      (node (ref "MOD1") (pin "H3") (pinfunction "DGND_H3") (pintype "passive"))
      (node (ref "MOD1") (pin "H4") (pinfunction "DGND_H4") (pintype "passive"))
      (node (ref "MOD1") (pin "I2") (pinfunction "DGND_I2") (pintype "passive"))
      (node (ref "MOD1") (pin "I4") (pinfunction "DGND_I4") (pintype "passive"))
      (node (ref "P3") (pin "1") (pinfunction "1_1") (pintype "passive"))
      (node (ref "P4") (pin "6") (pinfunction "6_6") (pintype "passive"))
      (node (ref "Q6") (pin "2") (pinfunction "S_2") (pintype "passive"))
      (node (ref "Q7") (pin "2") (pinfunction "S_2") (pintype "passive"))
      (node (ref "R55") (pin "1") (pinfunction "1_1") (pintype "passive"))
      (node (ref "R64") (pin "1") (pinfunction "1_1") (pintype "passive"))
      (node (ref "R66") (pin "2") (pinfunction "2_2") (pintype "passive"))
      (node (ref "R67") (pin "2") (pinfunction "2_2") (pintype "passive"))
      (node (ref "SW2") (pin "3") (pinfunction "3_3") (pintype "passive"))
      (node (ref "SW2") (pin "4") (pinfunction "4_4") (pintype "passive"))
      (node (ref "SW3") (pin "1") (pinfunction "1_1") (pintype "passive"))
      (node (ref "SW3") (pin "2") (pinfunction "2_2") (pintype "passive"))
      (node (ref "U29") (pin "3") (pinfunction "GND_3") (pintype "passive"))
      (node (ref "U29") (pin "8") (pinfunction "GND_8") (pintype "passive"))
      (node (ref "U30") (pin "3") (pinfunction "GND_3") (pintype "passive"))
      (node (ref "U30") (pin "8") (pinfunction "GND_8") (pintype "passive"))
    )
    (net (code "74") (name "Net-(D17-Pad1)") (class "Default")
      (node (ref "D17") (pin "1") (pinfunction "1_1") (pintype "passive"))
      (node (ref "P3") (pin "3") (pinfunction "3_3") (pintype "passive"))
    )
    (net (code "75") (name "Net-(D18-Pad2)") (class "Default")
      (node (ref "D18") (pin "2") (pinfunction "2_2") (pintype "passive"))
      (node (ref "R62") (pin "1") (pinfunction "1_1") (pintype "passive"))
    )
    (net (code "76") (name "Net-(D19-Pad2)") (class "Default")
      (node (ref "D19") (pin "2") (pinfunction "2_2") (pintype "passive"))
      (node (ref "R63") (pin "1") (pinfunction "1_1") (pintype "passive"))
    )
    (net (code "77") (name "Net-(D20-Pad1)") (class "Default")
      (node (ref "D20") (pin "1") (pinfunction "1_1") (pintype "passive"))
      (node (ref "P4") (pin "1") (pinfunction "1_1") (pintype "passive"))
    )
    (net (code "78") (name "Net-(MOD1B-UART0_CTS#)") (class "Default")
      (node (ref "MOD1") (pin "44") (pinfunction "UART0_CTS#_44") (pintype "passive"))
      (node (ref "P3") (pin "2") (pinfunction "2_2") (pintype "passive"))
    )
    (net (code "79") (name "Net-(MOD1B-UART0_RTS#)") (class "Default")
      (node (ref "MOD1") (pin "45") (pinfunction "UART0_RTS#_45") (pintype "passive"))
      (node (ref "R54") (pin "1") (pinfunction "1_1") (pintype "passive"))
    )
    (net (code "80") (name "Net-(MOD1B-UART0_RX)") (class "Default")
      (node (ref "MOD1") (pin "47") (pinfunction "UART0_RX_47") (pintype "passive"))
      (node (ref "P3") (pin "4") (pinfunction "4_4") (pintype "passive"))
      (node (ref "R55") (pin "2") (pinfunction "2_2") (pintype "passive"))
    )
    (net (code "81") (name "Net-(MOD1B-UART0_TX)") (class "Default")
      (node (ref "MOD1") (pin "46") (pinfunction "UART0_TX_46") (pintype "passive"))
      (node (ref "P3") (pin "5") (pinfunction "5_5") (pintype "passive"))
    )
    (net (code "82") (name "Net-(MOD1C-LCD_DATA2)") (class "Default")
      (node (ref "MOD1") (pin "95") (pinfunction "LCD_DATA2_95") (pintype "passive"))
      (node (ref "R65") (pin "2") (pinfunction "2_2") (pintype "passive"))
    )
    (net (code "83") (name "Net-(MOD1C-USB1_ID)") (class "Default")
      (node (ref "MOD1") (pin "89") (pinfunction "USB1_ID_89") (pintype "passive"))
      (node (ref "R64") (pin "2") (pinfunction "2_2") (pintype "passive"))
    )
    (net (code "84") (name "Net-(P3-Pad6)") (class "Default")
      (node (ref "P3") (pin "6") (pinfunction "6_6") (pintype "passive"))
      (node (ref "R54") (pin "2") (pinfunction "2_2") (pintype "passive"))
    )
    (net (code "85") (name "Net-(Q6-D)") (class "Default")
      (node (ref "D18") (pin "1") (pinfunction "1_1") (pintype "passive"))
      (node (ref "Q6") (pin "3") (pinfunction "D_3") (pintype "passive"))
    )
    (net (code "86") (name "Net-(Q7-D)") (class "Default")
      (node (ref "D19") (pin "1") (pinfunction "1_1") (pintype "passive"))
      (node (ref "Q7") (pin "3") (pinfunction "D_3") (pintype "passive"))
    )
    (net (code "87") (name "unconnected-(MOD1A-BKL_FB_WLED-Pad16)") (class "Default")
      (node (ref "MOD1") (pin "16") (pinfunction "BKL_FB_WLED_16") (pintype "passive"))
    )
    (net (code "88") (name "unconnected-(MOD1A-BKL_ISET1-Pad14)") (class "Default")
      (node (ref "MOD1") (pin "14") (pinfunction "BKL_ISET1_14") (pintype "passive"))
    )
    (net (code "89") (name "unconnected-(MOD1A-BKL_ISET2-Pad13)") (class "Default")
      (node (ref "MOD1") (pin "13") (pinfunction "BKL_ISET2_13") (pintype "passive"))
    )
    (net (code "90") (name "unconnected-(MOD1A-BKL_ISINK1-Pad31)") (class "Default")
      (node (ref "MOD1") (pin "31") (pinfunction "BKL_ISINK1_31") (pintype "passive"))
    )
    (net (code "91") (name "unconnected-(MOD1A-BKL_ISINK2-Pad30)") (class "Default")
      (node (ref "MOD1") (pin "30") (pinfunction "BKL_ISINK2_30") (pintype "passive"))
    )
    (net (code "92") (name "unconnected-(MOD1A-BKL_L4-Pad15)") (class "Default")
      (node (ref "MOD1") (pin "15") (pinfunction "BKL_L4_15") (pintype "passive"))
    )
    (net (code "93") (name "unconnected-(MOD1A-I2C0_SCL-Pad32)") (class "Default")
      (node (ref "MOD1") (pin "32") (pinfunction "I2C0_SCL_32") (pintype "passive"))
    )
    (net (code "94") (name "unconnected-(MOD1A-I2C0_SDA-Pad33)") (class "Default")
      (node (ref "MOD1") (pin "33") (pinfunction "I2C0_SDA_33") (pintype "passive"))
    )
    (net (code "95") (name "unconnected-(MOD1B-AIN0-Pad59)") (class "Default")
      (node (ref "MOD1") (pin "59") (pinfunction "AIN0_59") (pintype "passive+no_connect"))
    )
    (net (code "96") (name "unconnected-(MOD1B-AIN1-Pad84)") (class "Default")
      (node (ref "MOD1") (pin "84") (pinfunction "AIN1_84") (pintype "passive+no_connect"))
    )
    (net (code "97") (name "unconnected-(MOD1B-AIN2-Pad58)") (class "Default")
      (node (ref "MOD1") (pin "58") (pinfunction "AIN2_58") (pintype "passive+no_connect"))
    )
    (net (code "98") (name "unconnected-(MOD1B-AIN3-Pad83)") (class "Default")
      (node (ref "MOD1") (pin "83") (pinfunction "AIN3_83") (pintype "passive+no_connect"))
    )
    (net (code "99") (name "unconnected-(MOD1B-AIN4-Pad57)") (class "Default")
      (node (ref "MOD1") (pin "57") (pinfunction "AIN4_57") (pintype "passive+no_connect"))
    )
    (net (code "100") (name "unconnected-(MOD1B-AIN5-Pad82)") (class "Default")
      (node (ref "MOD1") (pin "82") (pinfunction "AIN5_82") (pintype "passive+no_connect"))
    )
    (net (code "101") (name "unconnected-(MOD1B-AIN6-Pad56)") (class "Default")
      (node (ref "MOD1") (pin "56") (pinfunction "AIN6_56") (pintype "passive+no_connect"))
    )
    (net (code "102") (name "unconnected-(MOD1B-BAT1-Pad60)") (class "Default")
      (node (ref "MOD1") (pin "60") (pinfunction "BAT1_60") (pintype "passive+no_connect"))
    )
    (net (code "103") (name "unconnected-(MOD1B-BAT_SENSE-Pad61)") (class "Default")
      (node (ref "MOD1") (pin "61") (pinfunction "BAT_SENSE_61") (pintype "passive+no_connect"))
    )
    (net (code "104") (name "unconnected-(MOD1B-BAT_TS-Pad62)") (class "Default")
      (node (ref "MOD1") (pin "62") (pinfunction "BAT_TS_62") (pintype "passive+no_connect"))
    )
    (net (code "105") (name "unconnected-(MOD1B-EHRPWM1A-Pad38)") (class "Default")
      (node (ref "MOD1") (pin "38") (pinfunction "EHRPWM1A_38") (pintype "passive+no_connect"))
    )
    (net (code "106") (name "unconnected-(MOD1B-EHRPWM1B-Pad39)") (class "Default")
      (node (ref "MOD1") (pin "39") (pinfunction "EHRPWM1B_39") (pintype "passive+no_connect"))
    )
    (net (code "107") (name "unconnected-(MOD1B-GPIO0_7SRC-Pad68)") (class "Default")
      (node (ref "MOD1") (pin "68") (pinfunction "GPIO0_7SRC_68") (pintype "passive+no_connect"))
    )
    (net (code "108") (name "unconnected-(MOD1B-I2C1_SCL-Pad50)") (class "Default")
      (node (ref "MOD1") (pin "50") (pinfunction "I2C1_SCL_50") (pintype "passive+no_connect"))
    )
    (net (code "109") (name "unconnected-(MOD1B-I2C1_SDA-Pad49)") (class "Default")
      (node (ref "MOD1") (pin "49") (pinfunction "I2C1_SDA_49") (pintype "passive+no_connect"))
    )
    (net (code "110") (name "unconnected-(MOD1B-JTAG_EMU0-Pad77)") (class "Default")
      (node (ref "MOD1") (pin "77") (pinfunction "JTAG_EMU0_77") (pintype "passive+no_connect"))
    )
    (net (code "111") (name "unconnected-(MOD1B-JTAG_EMU1-Pad51)") (class "Default")
      (node (ref "MOD1") (pin "51") (pinfunction "JTAG_EMU1_51") (pintype "passive+no_connect"))
    )
    (net (code "112") (name "unconnected-(MOD1B-JTAG_TCK-Pad52)") (class "Default")
      (node (ref "MOD1") (pin "52") (pinfunction "JTAG_TCK_52") (pintype "passive+no_connect"))
    )
    (net (code "113") (name "unconnected-(MOD1B-JTAG_TDI-Pad78)") (class "Default")
      (node (ref "MOD1") (pin "78") (pinfunction "JTAG_TDI_78") (pintype "passive+no_connect"))
    )
    (net (code "114") (name "unconnected-(MOD1B-JTAG_TDO-Pad53)") (class "Default")
      (node (ref "MOD1") (pin "53") (pinfunction "JTAG_TDO_53") (pintype "passive+no_connect"))
    )
    (net (code "115") (name "unconnected-(MOD1B-JTAG_TMS-Pad79)") (class "Default")
      (node (ref "MOD1") (pin "79") (pinfunction "JTAG_TMS_79") (pintype "passive+no_connect"))
    )
    (net (code "116") (name "unconnected-(MOD1B-JTAG_TRSTn-Pad54)") (class "Default")
      (node (ref "MOD1") (pin "54") (pinfunction "JTAG_TRSTn_54") (pintype "passive+no_connect"))
    )
    (net (code "117") (name "unconnected-(MOD1B-XDMA_EVENT_INTR0-Pad43)") (class "Default")
      (node (ref "MOD1") (pin "43") (pinfunction "XDMA_EVENT_INTR0_43") (pintype "passive+no_connect"))
    )
    (net (code "118") (name "unconnected-(MOD1C-GPIO3_18-Pad85)") (class "Default")
      (node (ref "MOD1") (pin "85") (pinfunction "GPIO3_18_85") (pintype "passive"))
    )
    (net (code "119") (name "unconnected-(MOD1C-GPIO3_20-Pad87)") (class "Default")
      (node (ref "MOD1") (pin "87") (pinfunction "GPIO3_20_87") (pintype "passive"))
    )
    (net (code "120") (name "unconnected-(MOD1C-LCD_DATA0-Pad94)") (class "Default")
      (node (ref "MOD1") (pin "94") (pinfunction "LCD_DATA0_94") (pintype "passive"))
    )
    (net (code "121") (name "unconnected-(MOD1C-LCD_DATA1-Pad111)") (class "Default")
      (node (ref "MOD1") (pin "111") (pinfunction "LCD_DATA1_111") (pintype "passive"))
    )
    (net (code "122") (name "unconnected-(MOD1C-LCD_DATA3-Pad112)") (class "Default")
      (node (ref "MOD1") (pin "112") (pinfunction "LCD_DATA3_112") (pintype "passive"))
    )
    (net (code "123") (name "unconnected-(MOD1C-LCD_DATA4-Pad96)") (class "Default")
      (node (ref "MOD1") (pin "96") (pinfunction "LCD_DATA4_96") (pintype "passive"))
    )
    (net (code "124") (name "unconnected-(MOD1C-LCD_DATA5-Pad113)") (class "Default")
      (node (ref "MOD1") (pin "113") (pinfunction "LCD_DATA5_113") (pintype "passive"))
    )
    (net (code "125") (name "unconnected-(MOD1C-LCD_DATA6-Pad97)") (class "Default")
      (node (ref "MOD1") (pin "97") (pinfunction "LCD_DATA6_97") (pintype "passive"))
    )
    (net (code "126") (name "unconnected-(MOD1C-LCD_DATA7-Pad114)") (class "Default")
      (node (ref "MOD1") (pin "114") (pinfunction "LCD_DATA7_114") (pintype "passive"))
    )
    (net (code "127") (name "unconnected-(MOD1C-LCD_DATA8-Pad98)") (class "Default")
      (node (ref "MOD1") (pin "98") (pinfunction "LCD_DATA8_98") (pintype "passive"))
    )
    (net (code "128") (name "unconnected-(MOD1C-LCD_DATA9-Pad115)") (class "Default")
      (node (ref "MOD1") (pin "115") (pinfunction "LCD_DATA9_115") (pintype "passive"))
    )
    (net (code "129") (name "unconnected-(MOD1C-LCD_DATA10-Pad99)") (class "Default")
      (node (ref "MOD1") (pin "99") (pinfunction "LCD_DATA10_99") (pintype "passive"))
    )
    (net (code "130") (name "unconnected-(MOD1C-LCD_DATA11-Pad116)") (class "Default")
      (node (ref "MOD1") (pin "116") (pinfunction "LCD_DATA11_116") (pintype "passive"))
    )
    (net (code "131") (name "unconnected-(MOD1C-LCD_DATA12-Pad100)") (class "Default")
      (node (ref "MOD1") (pin "100") (pinfunction "LCD_DATA12_100") (pintype "passive"))
    )
    (net (code "132") (name "unconnected-(MOD1C-LCD_DATA13-Pad117)") (class "Default")
      (node (ref "MOD1") (pin "117") (pinfunction "LCD_DATA13_117") (pintype "passive"))
    )
    (net (code "133") (name "unconnected-(MOD1C-LCD_DATA14-Pad101)") (class "Default")
      (node (ref "MOD1") (pin "101") (pinfunction "LCD_DATA14_101") (pintype "passive"))
    )
    (net (code "134") (name "unconnected-(MOD1C-LCD_DATA15-Pad118)") (class "Default")
      (node (ref "MOD1") (pin "118") (pinfunction "LCD_DATA15_118") (pintype "passive"))
    )
    (net (code "135") (name "unconnected-(MOD1C-USB1_CE-Pad108)") (class "Default")
      (node (ref "MOD1") (pin "108") (pinfunction "USB1_CE_108") (pintype "passive"))
    )
    (net (code "136") (name "unconnected-(MOD1D-EHRPWM2A-Pad154)") (class "Default")
      (node (ref "MOD1") (pin "154") (pinfunction "EHRPWM2A_154") (pintype "passive"))
    )
    (net (code "137") (name "unconnected-(MOD1D-EHRPWM2B-Pad155)") (class "Default")
      (node (ref "MOD1") (pin "155") (pinfunction "EHRPWM2B_155") (pintype "passive"))
    )
    (net (code "138") (name "unconnected-(MOD1D-GPIO0_26-Pad133)") (class "Default")
      (node (ref "MOD1") (pin "133") (pinfunction "GPIO0_26_133") (pintype "passive"))
    )
    (net (code "139") (name "unconnected-(MOD1D-GPIO1_12-Pad162)") (class "Default")
      (node (ref "MOD1") (pin "162") (pinfunction "GPIO1_12_162") (pintype "passive"))
    )
    (net (code "140") (name "unconnected-(MOD1D-HDMICLK_DISn-Pad136)") (class "Default")
      (node (ref "MOD1") (pin "136") (pinfunction "HDMICLK_DISn_136") (pintype "passive"))
    )
    (net (code "141") (name "unconnected-(MOD1D-HDMI_INT-Pad135)") (class "Default")
      (node (ref "MOD1") (pin "135") (pinfunction "HDMI_INT_135") (pintype "passive"))
    )
    (net (code "142") (name "unconnected-(MOD1D-LCDDE-Pad120)") (class "Default")
      (node (ref "MOD1") (pin "120") (pinfunction "LCDDE_120") (pintype "passive"))
    )
    (net (code "143") (name "unconnected-(MOD1D-LCDHSYNC-Pad145)") (class "Default")
      (node (ref "MOD1") (pin "145") (pinfunction "LCDHSYNC_145") (pintype "passive"))
    )
    (net (code "144") (name "unconnected-(MOD1D-LCDPCLK-Pad144)") (class "Default")
      (node (ref "MOD1") (pin "144") (pinfunction "LCDPCLK_144") (pintype "passive"))
    )
    (net (code "145") (name "unconnected-(MOD1D-LCDVSYNC-Pad146)") (class "Default")
      (node (ref "MOD1") (pin "146") (pinfunction "LCDVSYNC_146") (pintype "passive"))
    )
    (net (code "146") (name "unconnected-(MOD1D-MMC1_CLK-Pad131)") (class "Default")
      (node (ref "MOD1") (pin "131") (pinfunction "MMC1_CLK_131") (pintype "passive"))
    )
    (net (code "147") (name "unconnected-(MOD1D-MMC1_CMD-Pad156)") (class "Default")
      (node (ref "MOD1") (pin "156") (pinfunction "MMC1_CMD_156") (pintype "passive"))
    )
    (net (code "148") (name "unconnected-(MOD1D-MMC1_DAT0-Pad123)") (class "Default")
      (node (ref "MOD1") (pin "123") (pinfunction "MMC1_DAT0_123") (pintype "passive"))
    )
    (net (code "149") (name "unconnected-(MOD1D-MMC1_DAT1-Pad124)") (class "Default")
      (node (ref "MOD1") (pin "124") (pinfunction "MMC1_DAT1_124") (pintype "passive"))
    )
    (net (code "150") (name "unconnected-(MOD1D-MMC1_DAT2-Pad125)") (class "Default")
      (node (ref "MOD1") (pin "125") (pinfunction "MMC1_DAT2_125") (pintype "passive"))
    )
    (net (code "151") (name "unconnected-(MOD1D-MMC1_DAT3-Pad126)") (class "Default")
      (node (ref "MOD1") (pin "126") (pinfunction "MMC1_DAT3_126") (pintype "passive"))
    )
    (net (code "152") (name "unconnected-(MOD1D-MMC1_DAT4-Pad127)") (class "Default")
      (node (ref "MOD1") (pin "127") (pinfunction "MMC1_DAT4_127") (pintype "passive"))
    )
    (net (code "153") (name "unconnected-(MOD1D-MMC1_DAT5-Pad128)") (class "Default")
      (node (ref "MOD1") (pin "128") (pinfunction "MMC1_DAT5_128") (pintype "passive"))
    )
    (net (code "154") (name "unconnected-(MOD1D-MMC1_DAT6-Pad129)") (class "Default")
      (node (ref "MOD1") (pin "129") (pinfunction "MMC1_DAT6_129") (pintype "passive"))
    )
    (net (code "155") (name "unconnected-(MOD1D-MMC1_DAT7-Pad130)") (class "Default")
      (node (ref "MOD1") (pin "130") (pinfunction "MMC1_DAT7_130") (pintype "passive"))
    )
    (net (code "156") (name "unconnected-(MOD1D-TIMER7-Pad151)") (class "Default")
      (node (ref "MOD1") (pin "151") (pinfunction "TIMER7_151") (pintype "passive"))
    )
    (net (code "157") (name "unconnected-(MOD1D-USB0_CE-Pad143)") (class "Default")
      (node (ref "MOD1") (pin "143") (pinfunction "USB0_CE_143") (pintype "passive"))
    )
    (net (code "158") (name "unconnected-(MOD1D-USB0_DRVVBUS-Pad168)") (class "Default")
      (node (ref "MOD1") (pin "168") (pinfunction "USB0_DRVVBUS_168") (pintype "passive"))
    )
    (net (code "159") (name "unconnected-(MOD1D-USB0_ID-Pad167)") (class "Default")
      (node (ref "MOD1") (pin "167") (pinfunction "USB0_ID_167") (pintype "passive+no_connect"))
    )
    (net (code "160") (name "unconnected-(MOD1D-USB0_VBUS-Pad142)") (class "Default")
      (node (ref "MOD1") (pin "142") (pinfunction "USB0_VBUS_142") (pintype "passive"))
    )
    (net (code "161") (name "unconnected-(MOD1D-USR2-Pad165)") (class "Default")
      (node (ref "MOD1") (pin "165") (pinfunction "USR2_165") (pintype "passive"))
    )
    (net (code "162") (name "unconnected-(MOD1D-USR3-Pad141)") (class "Default")
      (node (ref "MOD1") (pin "141") (pinfunction "USR3_141") (pintype "passive"))
    )
    (net (code "163") (name "unconnected-(MOD1D-eMMC_RSTn-Pad122)") (class "Default")
      (node (ref "MOD1") (pin "122") (pinfunction "eMMC_RSTn_122") (pintype "passive"))
    )
    (net (code "164") (name "unconnected-(MOD1E-SYS_5V-PadB4)") (class "Default")
      (node (ref "MOD1") (pin "B4") (pinfunction "SYS_5V_B4") (pintype "passive"))
    )
    (net (code "165") (name "unconnected-(MOD1E-VDDS_DDR-PadI3)") (class "Default")
      (node (ref "MOD1") (pin "I3") (pinfunction "VDDS_DDR_I3") (pintype "passive"))
    )
    (net (code "166") (name "unconnected-(MOD1E-VDDS_DDR-PadI5)") (class "Default")
      (node (ref "MOD1") (pin "I5") (pinfunction "VDDS_DDR_I5") (pintype "passive"))
    )
    (net (code "167") (name "unconnected-(MOD1E-VDD_1V8-PadC3)") (class "Default")
      (node (ref "MOD1") (pin "C3") (pinfunction "VDD_1V8_C3") (pintype "passive"))
    )
    (net (code "168") (name "unconnected-(MOD1E-VDD_1V8-PadC4)") (class "Default")
      (node (ref "MOD1") (pin "C4") (pinfunction "VDD_1V8_C4") (pintype "passive"))
    )
    (net (code "169") (name "unconnected-(MOD1E-VDD_CORE-PadA3)") (class "Default")
      (node (ref "MOD1") (pin "A3") (pinfunction "VDD_CORE_A3") (pintype "passive"))
    )
    (net (code "170") (name "unconnected-(MOD1E-VDD_CORE-PadH1)") (class "Default")
      (node (ref "MOD1") (pin "H1") (pinfunction "VDD_CORE_H1") (pintype "passive"))
    )
    (net (code "171") (name "unconnected-(MOD1E-VDD_CORE-PadI1)") (class "Default")
      (node (ref "MOD1") (pin "I1") (pinfunction "VDD_CORE_I1") (pintype "passive"))
    )
    (net (code "172") (name "unconnected-(MOD1E-VDD_MPU-PadB3)") (class "Default")
      (node (ref "MOD1") (pin "B3") (pinfunction "VDD_MPU_B3") (pintype "passive"))
    )
    (net (code "173") (name "unconnected-(MOD1E-VDD_PLL-PadC2)") (class "Default")
      (node (ref "MOD1") (pin "C2") (pinfunction "VDD_PLL_C2") (pintype "passive"))
    )
    (net (code "174") (name "unconnected-(MOD1E-VDD_S-PadC5)") (class "Default")
      (node (ref "MOD1") (pin "C5") (pinfunction "VDD_S_C5") (pintype "passive"))
    )
    (net (code "175") (name "unconnected-(MOD1E-VDD_S-PadG3)") (class "Default")
      (node (ref "MOD1") (pin "G3") (pinfunction "VDD_S_G3") (pintype "passive"))
    )
    (net (code "176") (name "unconnected-(U29-IO1-Pad1)") (class "Default")
      (node (ref "U29") (pin "1") (pinfunction "IO1_1") (pintype "passive+no_connect"))
    )
    (net (code "177") (name "unconnected-(U29-NC-Pad10)") (class "Default")
      (node (ref "U29") (pin "10") (pinfunction "NC_10") (pintype "passive+no_connect"))
    )
  )
)
